# lightningbugsinajar.net
KiCad netlist of a schematic drawn in EAGLE
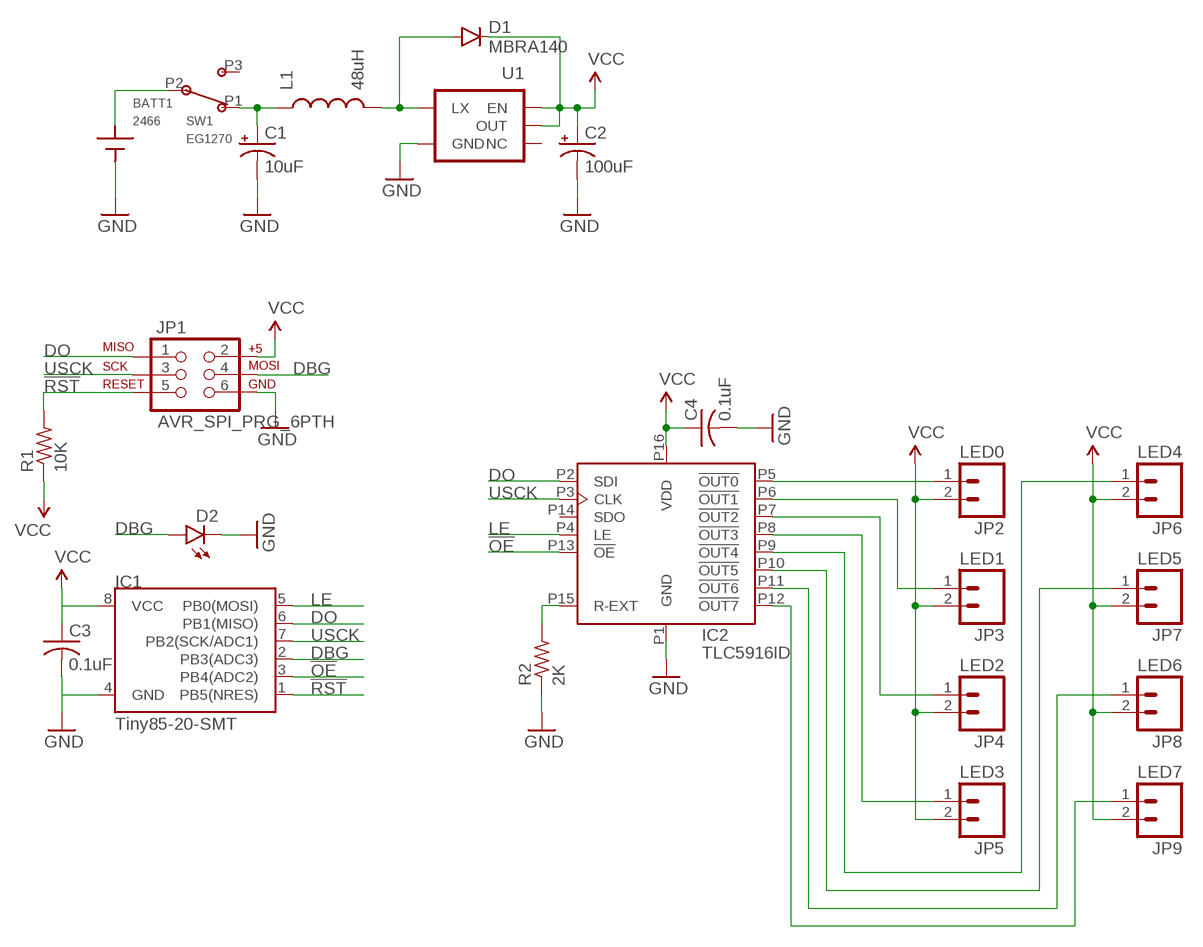
[diagram p0: schematic, sheet 1]

(export (version "E")
  (design (tool "Eeschema 10.0.6"))
  (components
    (comp (ref "BATT1")
      (value "2466")
      (footprint "eagle-import:2466")
      (libsource (lib "eagle-import") (part "2466"))
    )
    (comp (ref "C1")
      (value "10uF")
      (footprint "eagle-import:EIA3528")
      (libsource (lib "eagle-import") (part "CAP_POL3528"))
    )
    (comp (ref "C2")
      (value "100uF")
      (footprint "eagle-import:EIA3528")
      (libsource (lib "eagle-import") (part "CAP_POL3528"))
    )
    (comp (ref "C3")
      (value "0.1uF")
      (footprint "eagle-import:C0805")
      (libsource (lib "eagle-import") (part "C-USC0805"))
    )
    (comp (ref "C4")
      (value "0.1uF")
      (footprint "eagle-import:C0805")
      (libsource (lib "eagle-import") (part "C-USC0805"))
    )
    (comp (ref "D1")
      (value "MBRA140")
      (footprint "eagle-import:SMA-DIODE")
      (libsource (lib "eagle-import") (part "DIODESMA"))
    )
    (comp (ref "D2")
      (value "LED3MM")
      (footprint "eagle-import:LED3MM")
      (libsource (lib "eagle-import") (part "LED3MM"))
    )
    (comp (ref "IC1")
      (value "Tiny85-20-SMT")
      (footprint "eagle-import:SO08-EIAJ")
      (libsource (lib "eagle-import") (part "ATTINY45TINY85-20-SMT"))
    )
    (comp (ref "IC2")
      (value "TLC5916ID")
      (footprint "eagle-import:SOIC-16")
      (libsource (lib "eagle-import") (part "TLC591?ID6"))
    )
    (comp (ref "JP1")
      (value "AVR_SPI_PRG_6PTH")
      (footprint "eagle-import:2X3")
      (libsource (lib "eagle-import") (part "AVR_SPI_PRG_6PTH"))
    )
    (comp (ref "JP2")
      (value "LED0")
      (footprint "eagle-import:1X02")
      (libsource (lib "eagle-import") (part "M02PTH"))
    )
    (comp (ref "JP3")
      (value "LED1")
      (footprint "eagle-import:1X02")
      (libsource (lib "eagle-import") (part "M02PTH"))
    )
    (comp (ref "JP4")
      (value "LED2")
      (footprint "eagle-import:1X02")
      (libsource (lib "eagle-import") (part "M02PTH"))
    )
    (comp (ref "JP5")
      (value "LED3")
      (footprint "eagle-import:1X02")
      (libsource (lib "eagle-import") (part "M02PTH"))
    )
    (comp (ref "JP6")
      (value "LED4")
      (footprint "eagle-import:1X02")
      (libsource (lib "eagle-import") (part "M02PTH"))
    )
    (comp (ref "JP7")
      (value "LED5")
      (footprint "eagle-import:1X02")
      (libsource (lib "eagle-import") (part "M02PTH"))
    )
    (comp (ref "JP8")
      (value "LED6")
      (footprint "eagle-import:1X02")
      (libsource (lib "eagle-import") (part "M02PTH"))
    )
    (comp (ref "JP9")
      (value "LED7")
      (footprint "eagle-import:1X02")
      (libsource (lib "eagle-import") (part "M02PTH"))
    )
    (comp (ref "L1")
      (value "48uH")
      (footprint "eagle-import:CR54")
      (libsource (lib "eagle-import") (part "INDUCTORCR54"))
    )
    (comp (ref "R1")
      (value "10K")
      (footprint "eagle-import:R0805")
      (libsource (lib "eagle-import") (part "R-US_R0805"))
    )
    (comp (ref "R2")
      (value "2K")
      (footprint "eagle-import:R0805")
      (libsource (lib "eagle-import") (part "R-US_R0805"))
    )
    (comp (ref "SW1")
      (value "EG1270")
      (footprint "eagle-import:EG1270")
      (libsource (lib "eagle-import") (part "EG1270"))
    )
    (comp (ref "U1")
      (value "V_REG_NCP1400SOT23-5")
      (footprint "eagle-import:SOT23-5")
      (libsource (lib "eagle-import") (part "V_REG_NCP1400SOT23-5"))
    )
  )
  (nets
    (net (code "1") (name "/3") (class "Default")
      (node (ref "SW1") (pin "P3") (pinfunction "3_P3") (pintype "power_in"))
    )
    (net (code "2") (name "/DBG") (class "Default")
      (node (ref "D2") (pin "A") (pinfunction "A_A") (pintype "passive"))
      (node (ref "IC1") (pin "2") (pinfunction "PB3(ADC3)_2") (pintype "bidirectional"))
      (node (ref "JP1") (pin "4") (pinfunction "4_4") (pintype "passive"))
    )
    (net (code "3") (name "/DO") (class "Default")
      (node (ref "IC1") (pin "6") (pinfunction "PB1(MISO)_6") (pintype "bidirectional"))
      (node (ref "IC2") (pin "P2") (pinfunction "SDI_P2") (pintype "input"))
      (node (ref "JP1") (pin "1") (pinfunction "1_1") (pintype "passive"))
    )
    (net (code "4") (name "/LE") (class "Default")
      (node (ref "IC1") (pin "5") (pinfunction "PB0(MOSI)_5") (pintype "bidirectional"))
      (node (ref "IC2") (pin "P4") (pinfunction "LE_P4") (pintype "input"))
    )
    (net (code "5") (name "/USCK") (class "Default")
      (node (ref "IC1") (pin "7") (pinfunction "PB2(SCK/ADC1)_7") (pintype "bidirectional"))
      (node (ref "IC2") (pin "P3") (pinfunction "CLK_P3") (pintype "input"))
      (node (ref "JP1") (pin "3") (pinfunction "3_3") (pintype "passive"))
    )
    (net (code "6") (name "/~{OE}") (class "Default")
      (node (ref "IC1") (pin "3") (pinfunction "PB4(ADC2)_3") (pintype "bidirectional"))
      (node (ref "IC2") (pin "P13") (pinfunction "~{OE}_P13") (pintype "input"))
    )
    (net (code "7") (name "/~{RST}") (class "Default")
      (node (ref "IC1") (pin "1") (pinfunction "PB5(NRES)_1") (pintype "bidirectional"))
      (node (ref "JP1") (pin "5") (pinfunction "5_5") (pintype "passive"))
      (node (ref "R1") (pin "2") (pinfunction "2_2") (pintype "passive"))
    )
    (net (code "8") (name "GND") (class "Default")
      (node (ref "BATT1") (pin "NEG") (pinfunction "NEG_NEG") (pintype "power_in"))
      (node (ref "C1") (pin "C") (pinfunction "-_C") (pintype "passive"))
      (node (ref "C2") (pin "C") (pinfunction "-_C") (pintype "passive"))
      (node (ref "C3") (pin "2") (pinfunction "2_2") (pintype "passive"))
      (node (ref "C4") (pin "2") (pinfunction "2_2") (pintype "passive"))
      (node (ref "D2") (pin "K") (pinfunction "C_K") (pintype "passive"))
      (node (ref "IC1") (pin "4") (pinfunction "GND_4") (pintype "bidirectional"))
      (node (ref "IC2") (pin "P1") (pinfunction "GND_P1") (pintype "power_in"))
      (node (ref "JP1") (pin "6") (pinfunction "6_6") (pintype "passive"))
      (node (ref "R2") (pin "1") (pinfunction "1_1") (pintype "passive"))
      (node (ref "U1") (pin "4") (pinfunction "GND_4") (pintype "input"))
    )
    (net (code "9") (name "Net-(C1-+)") (class "Default")
      (node (ref "C1") (pin "A") (pinfunction "+_A") (pintype "passive"))
      (node (ref "L1") (pin "P$1") (pinfunction "1_P$1") (pintype "passive"))
      (node (ref "SW1") (pin "P1") (pinfunction "1_P1") (pintype "power_in"))
    )
    (net (code "10") (name "Net-(IC2-R-EXT)") (class "Default")
      (node (ref "IC2") (pin "P15") (pinfunction "R-EXT_P15") (pintype "bidirectional"))
      (node (ref "R2") (pin "2") (pinfunction "2_2") (pintype "passive"))
    )
    (net (code "11") (name "Net-(IC2-~{OUT0})") (class "Default")
      (node (ref "IC2") (pin "P5") (pinfunction "~{OUT0}_P5") (pintype "bidirectional"))
      (node (ref "JP2") (pin "1") (pinfunction "1_1") (pintype "passive"))
    )
    (net (code "12") (name "Net-(IC2-~{OUT1})") (class "Default")
      (node (ref "IC2") (pin "P6") (pinfunction "~{OUT1}_P6") (pintype "bidirectional"))
      (node (ref "JP3") (pin "1") (pinfunction "1_1") (pintype "passive"))
    )
    (net (code "13") (name "Net-(IC2-~{OUT2})") (class "Default")
      (node (ref "IC2") (pin "P7") (pinfunction "~{OUT2}_P7") (pintype "bidirectional"))
      (node (ref "JP4") (pin "1") (pinfunction "1_1") (pintype "passive"))
    )
    (net (code "14") (name "Net-(IC2-~{OUT3})") (class "Default")
      (node (ref "IC2") (pin "P8") (pinfunction "~{OUT3}_P8") (pintype "bidirectional"))
      (node (ref "JP5") (pin "1") (pinfunction "1_1") (pintype "passive"))
    )
    (net (code "15") (name "Net-(IC2-~{OUT4})") (class "Default")
      (node (ref "IC2") (pin "P9") (pinfunction "~{OUT4}_P9") (pintype "bidirectional"))
      (node (ref "JP6") (pin "1") (pinfunction "1_1") (pintype "passive"))
    )
    (net (code "16") (name "Net-(IC2-~{OUT5})") (class "Default")
      (node (ref "IC2") (pin "P10") (pinfunction "~{OUT5}_P10") (pintype "bidirectional"))
      (node (ref "JP7") (pin "1") (pinfunction "1_1") (pintype "passive"))
    )
    (net (code "17") (name "Net-(IC2-~{OUT6})") (class "Default")
      (node (ref "IC2") (pin "P11") (pinfunction "~{OUT6}_P11") (pintype "bidirectional"))
      (node (ref "JP8") (pin "1") (pinfunction "1_1") (pintype "passive"))
    )
    (net (code "18") (name "Net-(IC2-~{OUT7})") (class "Default")
      (node (ref "IC2") (pin "P12") (pinfunction "~{OUT7}_P12") (pintype "bidirectional"))
      (node (ref "JP9") (pin "1") (pinfunction "1_1") (pintype "passive"))
    )
    (net (code "19") (name "Net-(L1-2)") (class "Default")
      (node (ref "D1") (pin "A") (pinfunction "A_A") (pintype "passive"))
      (node (ref "L1") (pin "P$2") (pinfunction "2_P$2") (pintype "passive"))
      (node (ref "U1") (pin "5") (pinfunction "LX_5") (pintype "input"))
    )
    (net (code "20") (name "Net-(SW1-COM)") (class "Default")
      (node (ref "BATT1") (pin "POS") (pinfunction "POS_POS") (pintype "power_in"))
      (node (ref "SW1") (pin "P2") (pinfunction "COM_P2") (pintype "passive"))
    )
    (net (code "21") (name "VCC") (class "Default")
      (node (ref "C2") (pin "A") (pinfunction "+_A") (pintype "passive"))
      (node (ref "C3") (pin "1") (pinfunction "1_1") (pintype "passive"))
      (node (ref "C4") (pin "1") (pinfunction "1_1") (pintype "passive"))
      (node (ref "D1") (pin "C") (pinfunction "C_C") (pintype "passive"))
      (node (ref "IC1") (pin "8") (pinfunction "VCC_8") (pintype "bidirectional"))
      (node (ref "IC2") (pin "P16") (pinfunction "VDD_P16") (pintype "power_in"))
      (node (ref "JP1") (pin "2") (pinfunction "2_2") (pintype "passive"))
      (node (ref "JP2") (pin "2") (pinfunction "2_2") (pintype "passive"))
      (node (ref "JP3") (pin "2") (pinfunction "2_2") (pintype "passive"))
      (node (ref "JP4") (pin "2") (pinfunction "2_2") (pintype "passive"))
      (node (ref "JP5") (pin "2") (pinfunction "2_2") (pintype "passive"))
      (node (ref "JP6") (pin "2") (pinfunction "2_2") (pintype "passive"))
      (node (ref "JP7") (pin "2") (pinfunction "2_2") (pintype "passive"))
      (node (ref "JP8") (pin "2") (pinfunction "2_2") (pintype "passive"))
      (node (ref "JP9") (pin "2") (pinfunction "2_2") (pintype "passive"))
      (node (ref "R1") (pin "1") (pinfunction "1_1") (pintype "passive"))
      (node (ref "U1") (pin "1") (pinfunction "EN_1") (pintype "input"))
      (node (ref "U1") (pin "2") (pinfunction "OUT_2") (pintype "passive"))
    )
    (net (code "22") (name "unconnected-(IC2-SDO-PadP14)") (class "Default")
      (node (ref "IC2") (pin "P14") (pinfunction "SDO_P14") (pintype "output"))
    )
    (net (code "23") (name "unconnected-(U1-NC-Pad3)") (class "Default")
      (node (ref "U1") (pin "3") (pinfunction "NC_3") (pintype "input"))
    )
  )
)
